# FAT_main_board.net
KiCad netlist of a schematic drawn in EAGLE
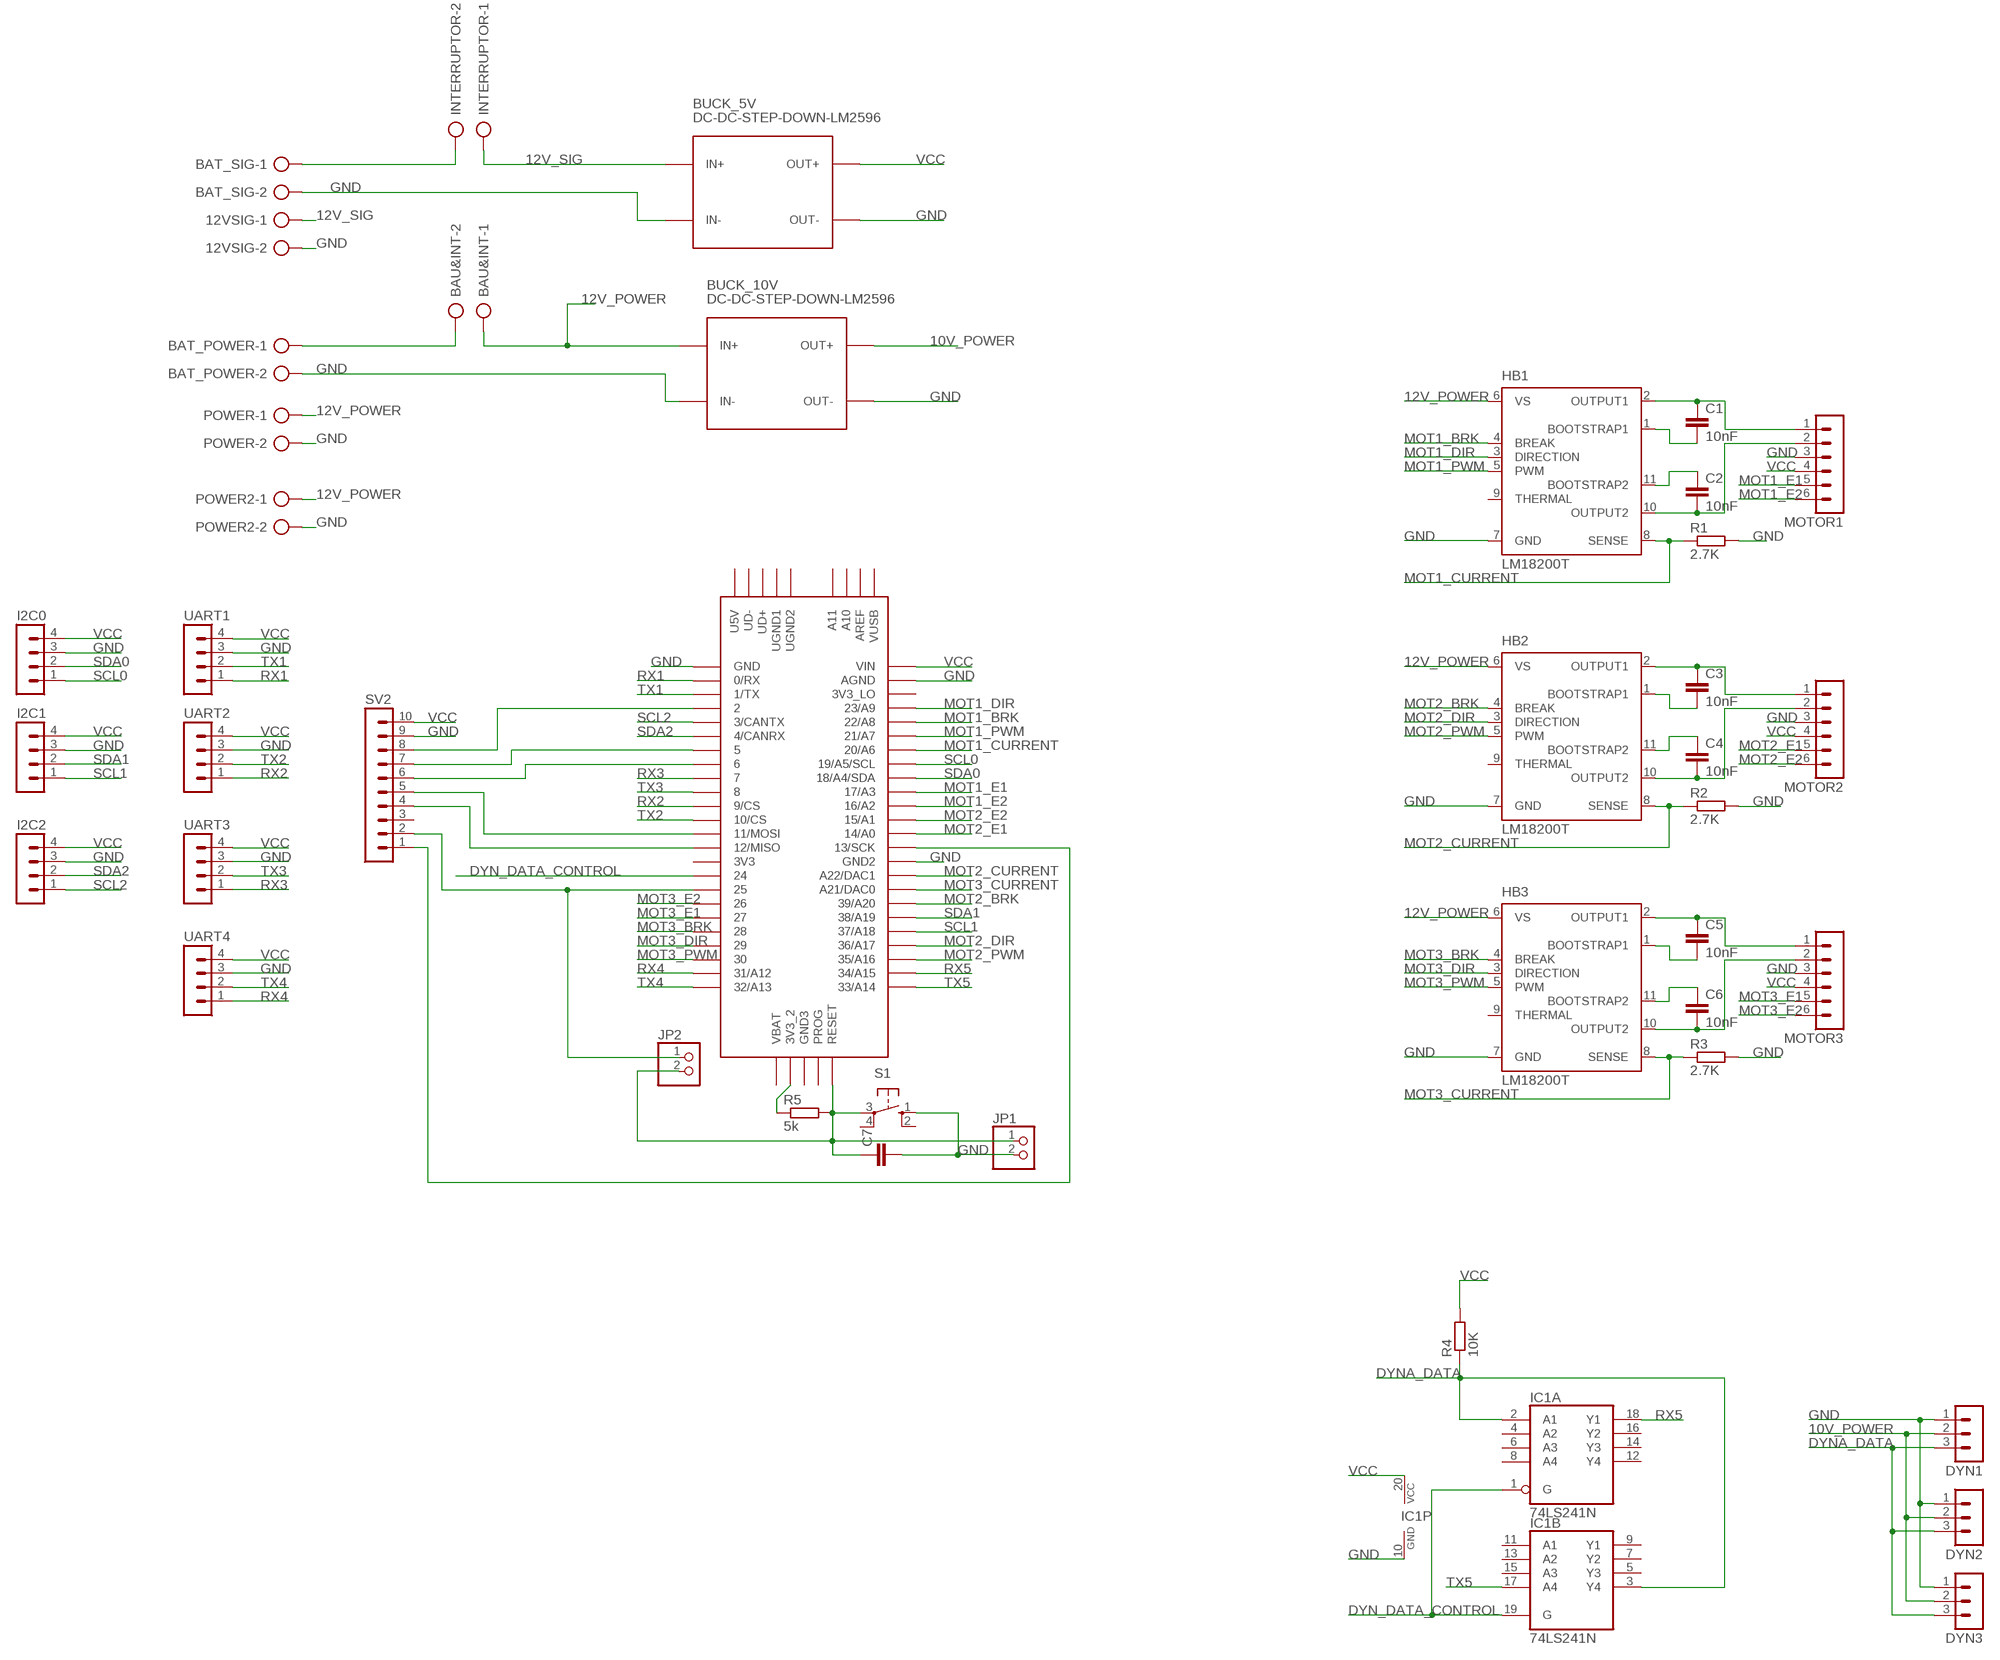
[diagram p0: schematic, sheet 1]

(export (version "E")
  (design (tool "Eeschema 10.0.6"))
  (components
    (comp (ref "12VSIG")
      (value "AK300/2")
      (footprint "eagle-import:AK300_2")
      (libsource (lib "eagle-import") (part "AK300/2"))
    )
    (comp (ref "BAT_POWER")
      (value "AK300/2")
      (footprint "eagle-import:AK300_2")
      (libsource (lib "eagle-import") (part "AK300/2"))
    )
    (comp (ref "BAT_SIG")
      (value "AK300/2")
      (footprint "eagle-import:AK300_2")
      (libsource (lib "eagle-import") (part "AK300/2"))
    )
    (comp (ref "BAU&INT")
      (value "AK300/2")
      (footprint "eagle-import:AK300_2")
      (libsource (lib "eagle-import") (part "AK300/2"))
    )
    (comp (ref "BUCK_5V")
      (value "DC-DC-STEP-DOWN-LM2596")
      (footprint "eagle-import:DC-DC-STEP-DOWN-LM2596")
      (libsource (lib "eagle-import") (part "DC-DC-STEP-DOWN-LM2596"))
    )
    (comp (ref "BUCK_10V")
      (value "DC-DC-STEP-DOWN-LM2596")
      (footprint "eagle-import:DC-DC-STEP-DOWN-LM2596")
      (libsource (lib "eagle-import") (part "DC-DC-STEP-DOWN-LM2596"))
    )
    (comp (ref "C1")
      (value "10nF")
      (footprint "eagle-import:C050-035X075")
      (libsource (lib "eagle-import") (part "resistor_C-EU050-035X075"))
    )
    (comp (ref "C2")
      (value "10nF")
      (footprint "eagle-import:C050-035X075")
      (libsource (lib "eagle-import") (part "resistor_C-EU050-035X075"))
    )
    (comp (ref "C3")
      (value "10nF")
      (footprint "eagle-import:C050-035X075")
      (libsource (lib "eagle-import") (part "resistor_C-EU050-035X075"))
    )
    (comp (ref "C4")
      (value "10nF")
      (footprint "eagle-import:C050-035X075")
      (libsource (lib "eagle-import") (part "resistor_C-EU050-035X075"))
    )
    (comp (ref "C5")
      (value "10nF")
      (footprint "eagle-import:C050-035X075")
      (libsource (lib "eagle-import") (part "resistor_C-EU050-035X075"))
    )
    (comp (ref "C6")
      (value "10nF")
      (footprint "eagle-import:C050-035X075")
      (libsource (lib "eagle-import") (part "resistor_C-EU050-035X075"))
    )
    (comp (ref "C7")
      (value "C-EU025-025X050")
      (footprint "eagle-import:C025-025X050")
      (libsource (lib "eagle-import") (part "C-EU025-025X050"))
    )
    (comp (ref "DYN1")
      (value "MA03-1")
      (footprint "eagle-import:MA03-1")
      (libsource (lib "eagle-import") (part "MA03-1"))
    )
    (comp (ref "DYN2")
      (value "MA03-1")
      (footprint "eagle-import:MA03-1")
      (libsource (lib "eagle-import") (part "MA03-1"))
    )
    (comp (ref "DYN3")
      (value "MA03-1")
      (footprint "eagle-import:MA03-1")
      (libsource (lib "eagle-import") (part "MA03-1"))
    )
    (comp (ref "HB1")
      (value "LM18200T")
      (footprint "eagle-import:TO-220-11")
      (libsource (lib "eagle-import") (part "LM18200T"))
    )
    (comp (ref "HB2")
      (value "LM18200T")
      (footprint "eagle-import:TO-220-11")
      (libsource (lib "eagle-import") (part "LM18200T"))
    )
    (comp (ref "HB3")
      (value "LM18200T")
      (footprint "eagle-import:TO-220-11")
      (libsource (lib "eagle-import") (part "LM18200T"))
    )
    (comp (ref "I2C0")
      (value "MA04-1")
      (footprint "eagle-import:MA04-1")
      (libsource (lib "eagle-import") (part "MA04-1"))
    )
    (comp (ref "I2C1")
      (value "MA04-1")
      (footprint "eagle-import:MA04-1")
      (libsource (lib "eagle-import") (part "MA04-1"))
    )
    (comp (ref "I2C2")
      (value "MA04-1")
      (footprint "eagle-import:MA04-1")
      (libsource (lib "eagle-import") (part "MA04-1"))
    )
    (comp (ref "IC1")
      (value "74LS241N")
      (footprint "eagle-import:DIL20")
      (libsource (lib "eagle-import") (part "74241NLS"))
    )
    (comp (ref "INTERRUPTOR")
      (value "AK300/2")
      (footprint "eagle-import:AK300_2")
      (libsource (lib "eagle-import") (part "AK300/2"))
    )
    (comp (ref "JP1")
      (value "PINHD-1X2")
      (footprint "eagle-import:1X02")
      (libsource (lib "eagle-import") (part "PINHD-1X2"))
    )
    (comp (ref "JP2")
      (value "PINHD-1X2")
      (footprint "eagle-import:1X02")
      (libsource (lib "eagle-import") (part "PINHD-1X2"))
    )
    (comp (ref "MOTOR1")
      (value "MA06-1")
      (footprint "eagle-import:MA06-1")
      (libsource (lib "eagle-import") (part "MA06-1"))
    )
    (comp (ref "MOTOR2")
      (value "MA06-1")
      (footprint "eagle-import:MA06-1")
      (libsource (lib "eagle-import") (part "MA06-1"))
    )
    (comp (ref "MOTOR3")
      (value "MA06-1")
      (footprint "eagle-import:MA06-1")
      (libsource (lib "eagle-import") (part "MA06-1"))
    )
    (comp (ref "POWER")
      (value "AK300/2")
      (footprint "eagle-import:AK300_2")
      (libsource (lib "eagle-import") (part "AK300/2"))
    )
    (comp (ref "POWER2")
      (value "AK300/2")
      (footprint "eagle-import:AK300_2")
      (libsource (lib "eagle-import") (part "AK300/2"))
    )
    (comp (ref "R1")
      (value "2.7K")
      (footprint "eagle-import:0204_7")
      (libsource (lib "eagle-import") (part "resistor_R-EU_0204/7"))
    )
    (comp (ref "R2")
      (value "2.7K")
      (footprint "eagle-import:0204_7")
      (libsource (lib "eagle-import") (part "resistor_R-EU_0204/7"))
    )
    (comp (ref "R3")
      (value "2.7K")
      (footprint "eagle-import:0204_7")
      (libsource (lib "eagle-import") (part "resistor_R-EU_0204/7"))
    )
    (comp (ref "R4")
      (value "10K")
      (footprint "eagle-import:0204_7")
      (libsource (lib "eagle-import") (part "resistor_R-EU_0204/7"))
    )
    (comp (ref "R5")
      (value "5k")
      (footprint "eagle-import:0204_7")
      (libsource (lib "eagle-import") (part "R-EU_0204/7"))
    )
    (comp (ref "S1")
      (value "10-XX")
      (footprint "eagle-import:B3F-10XX")
      (fields (field (name "MPN") "B3F-1000"))
      (libsource (lib "eagle-import") (part "10-XX"))
    )
    (comp (ref "SV2")
      (value "MA10-1")
      (footprint "eagle-import:MA10-1")
      (libsource (lib "eagle-import") (part "MA10-1"))
    )
    (comp (ref "U$1")
      (value "TEENSY_3.5/3.6")
      (footprint "eagle-import:TEENSY_3.5_3.6")
      (libsource (lib "eagle-import") (part "TEENSY_3.5/3.6"))
    )
    (comp (ref "UART1")
      (value "MA04-1")
      (footprint "eagle-import:MA04-1")
      (libsource (lib "eagle-import") (part "MA04-1"))
    )
    (comp (ref "UART2")
      (value "MA04-1")
      (footprint "eagle-import:MA04-1")
      (libsource (lib "eagle-import") (part "MA04-1"))
    )
    (comp (ref "UART3")
      (value "MA04-1")
      (footprint "eagle-import:MA04-1")
      (libsource (lib "eagle-import") (part "MA04-1"))
    )
    (comp (ref "UART4")
      (value "MA04-1")
      (footprint "eagle-import:MA04-1")
      (libsource (lib "eagle-import") (part "MA04-1"))
    )
  )
  (nets
    (net (code "1") (name "/10V_POWER") (class "Default")
      (node (ref "BUCK_10V") (pin "OUT+") (pinfunction "OUT+_OUT+") (pintype "bidirectional"))
      (node (ref "DYN1") (pin "2") (pinfunction "2_2") (pintype "passive"))
      (node (ref "DYN2") (pin "2") (pinfunction "2_2") (pintype "passive"))
      (node (ref "DYN3") (pin "2") (pinfunction "2_2") (pintype "passive"))
    )
    (net (code "2") (name "/12V_POWER") (class "Default")
      (node (ref "BAU&INT") (pin "1") (pinfunction "KL_1") (pintype "passive"))
      (node (ref "BUCK_10V") (pin "IN+") (pinfunction "IN+_IN+") (pintype "bidirectional"))
      (node (ref "HB1") (pin "6") (pinfunction "VS_6") (pintype "power_in"))
      (node (ref "HB2") (pin "6") (pinfunction "VS_6") (pintype "power_in"))
      (node (ref "HB3") (pin "6") (pinfunction "VS_6") (pintype "power_in"))
      (node (ref "POWER") (pin "1") (pinfunction "KL_1") (pintype "passive"))
      (node (ref "POWER2") (pin "1") (pinfunction "KL_1") (pintype "passive"))
    )
    (net (code "3") (name "/12V_SIG") (class "Default")
      (node (ref "12VSIG") (pin "1") (pinfunction "KL_1") (pintype "passive"))
      (node (ref "BUCK_5V") (pin "IN+") (pinfunction "IN+_IN+") (pintype "bidirectional"))
      (node (ref "INTERRUPTOR") (pin "1") (pinfunction "KL_1") (pintype "passive"))
    )
    (net (code "4") (name "/DYNA_DATA") (class "Default")
      (node (ref "DYN1") (pin "3") (pinfunction "3_3") (pintype "passive"))
      (node (ref "DYN2") (pin "3") (pinfunction "3_3") (pintype "passive"))
      (node (ref "DYN3") (pin "3") (pinfunction "3_3") (pintype "passive"))
      (node (ref "IC1") (pin "2") (pinfunction "A1_2") (pintype "input"))
      (node (ref "IC1") (pin "3") (pinfunction "Y4_3") (pintype "tri_state"))
      (node (ref "R4") (pin "1") (pinfunction "1_1") (pintype "passive"))
    )
    (net (code "5") (name "/DYN_DATA_CONTROL") (class "Default")
      (node (ref "IC1") (pin "1") (pinfunction "G_1") (pintype "input"))
      (node (ref "IC1") (pin "19") (pinfunction "G_19") (pintype "input"))
      (node (ref "U$1") (pin "24") (pinfunction "24_24") (pintype "bidirectional"))
    )
    (net (code "6") (name "/GND") (class "Default")
      (node (ref "12VSIG") (pin "2") (pinfunction "KL_2") (pintype "passive"))
      (node (ref "BAT_POWER") (pin "2") (pinfunction "KL_2") (pintype "passive"))
      (node (ref "BAT_SIG") (pin "2") (pinfunction "KL_2") (pintype "passive"))
      (node (ref "BUCK_10V") (pin "IN-") (pinfunction "IN-_IN-") (pintype "bidirectional"))
      (node (ref "BUCK_10V") (pin "OUT-") (pinfunction "OUT-_OUT-") (pintype "bidirectional"))
      (node (ref "BUCK_5V") (pin "IN-") (pinfunction "IN-_IN-") (pintype "bidirectional"))
      (node (ref "BUCK_5V") (pin "OUT-") (pinfunction "OUT-_OUT-") (pintype "bidirectional"))
      (node (ref "C7") (pin "2") (pinfunction "2_2") (pintype "passive"))
      (node (ref "DYN1") (pin "1") (pinfunction "1_1") (pintype "passive"))
      (node (ref "DYN2") (pin "1") (pinfunction "1_1") (pintype "passive"))
      (node (ref "DYN3") (pin "1") (pinfunction "1_1") (pintype "passive"))
      (node (ref "HB1") (pin "7") (pinfunction "GND_7") (pintype "power_in"))
      (node (ref "HB2") (pin "7") (pinfunction "GND_7") (pintype "power_in"))
      (node (ref "HB3") (pin "7") (pinfunction "GND_7") (pintype "power_in"))
      (node (ref "I2C0") (pin "3") (pinfunction "3_3") (pintype "passive"))
      (node (ref "I2C1") (pin "3") (pinfunction "3_3") (pintype "passive"))
      (node (ref "I2C2") (pin "3") (pinfunction "3_3") (pintype "passive"))
      (node (ref "IC1") (pin "10") (pinfunction "GND_10") (pintype "power_in"))
      (node (ref "JP1") (pin "2") (pinfunction "2_2") (pintype "passive"))
      (node (ref "MOTOR1") (pin "3") (pinfunction "3_3") (pintype "passive"))
      (node (ref "MOTOR2") (pin "3") (pinfunction "3_3") (pintype "passive"))
      (node (ref "MOTOR3") (pin "3") (pinfunction "3_3") (pintype "passive"))
      (node (ref "POWER") (pin "2") (pinfunction "KL_2") (pintype "passive"))
      (node (ref "POWER2") (pin "2") (pinfunction "KL_2") (pintype "passive"))
      (node (ref "R1") (pin "2") (pinfunction "2_2") (pintype "passive"))
      (node (ref "R2") (pin "2") (pinfunction "2_2") (pintype "passive"))
      (node (ref "R3") (pin "2") (pinfunction "2_2") (pintype "passive"))
      (node (ref "S1") (pin "1") (pinfunction "S_1") (pintype "passive"))
      (node (ref "SV2") (pin "9") (pinfunction "9_9") (pintype "passive"))
      (node (ref "U$1") (pin "AGND") (pinfunction "AGND_AGND") (pintype "bidirectional"))
      (node (ref "U$1") (pin "GND") (pinfunction "GND_GND") (pintype "bidirectional"))
      (node (ref "U$1") (pin "GND2") (pinfunction "GND2_GND2") (pintype "bidirectional"))
      (node (ref "UART1") (pin "3") (pinfunction "3_3") (pintype "passive"))
      (node (ref "UART2") (pin "3") (pinfunction "3_3") (pintype "passive"))
      (node (ref "UART3") (pin "3") (pinfunction "3_3") (pintype "passive"))
      (node (ref "UART4") (pin "3") (pinfunction "3_3") (pintype "passive"))
    )
    (net (code "7") (name "/MOT1_BRK") (class "Default")
      (node (ref "HB1") (pin "4") (pinfunction "BREAK_4") (pintype "input"))
      (node (ref "U$1") (pin "22/A8") (pinfunction "22/A8_22/A8") (pintype "bidirectional"))
    )
    (net (code "8") (name "/MOT1_CURRENT") (class "Default")
      (node (ref "HB1") (pin "8") (pinfunction "SENSE_8") (pintype "output"))
      (node (ref "R1") (pin "1") (pinfunction "1_1") (pintype "passive"))
      (node (ref "U$1") (pin "20/A6") (pinfunction "20/A6_20/A6") (pintype "bidirectional"))
    )
    (net (code "9") (name "/MOT1_DIR") (class "Default")
      (node (ref "HB1") (pin "3") (pinfunction "DIRECTION_3") (pintype "input"))
      (node (ref "U$1") (pin "23/A9") (pinfunction "23/A9_23/A9") (pintype "bidirectional"))
    )
    (net (code "10") (name "/MOT1_E1") (class "Default")
      (node (ref "MOTOR1") (pin "5") (pinfunction "5_5") (pintype "passive"))
      (node (ref "U$1") (pin "17/A3") (pinfunction "17/A3_17/A3") (pintype "bidirectional"))
    )
    (net (code "11") (name "/MOT1_E2") (class "Default")
      (node (ref "MOTOR1") (pin "6") (pinfunction "6_6") (pintype "passive"))
      (node (ref "U$1") (pin "16/A2") (pinfunction "16/A2_16/A2") (pintype "bidirectional"))
    )
    (net (code "12") (name "/MOT1_PWM") (class "Default")
      (node (ref "HB1") (pin "5") (pinfunction "PWM_5") (pintype "input"))
      (node (ref "U$1") (pin "21/A7") (pinfunction "21/A7_21/A7") (pintype "bidirectional"))
    )
    (net (code "13") (name "/MOT2_BRK") (class "Default")
      (node (ref "HB2") (pin "4") (pinfunction "BREAK_4") (pintype "input"))
      (node (ref "U$1") (pin "39/A20") (pinfunction "39/A20_39/A20") (pintype "bidirectional"))
    )
    (net (code "14") (name "/MOT2_CURRENT") (class "Default")
      (node (ref "HB2") (pin "8") (pinfunction "SENSE_8") (pintype "output"))
      (node (ref "R2") (pin "1") (pinfunction "1_1") (pintype "passive"))
      (node (ref "U$1") (pin "A22/DAC1") (pinfunction "A22/DAC1_A22/DAC1") (pintype "bidirectional"))
    )
    (net (code "15") (name "/MOT2_DIR") (class "Default")
      (node (ref "HB2") (pin "3") (pinfunction "DIRECTION_3") (pintype "input"))
      (node (ref "U$1") (pin "36/A17") (pinfunction "36/A17_36/A17") (pintype "bidirectional"))
    )
    (net (code "16") (name "/MOT2_E1") (class "Default")
      (node (ref "MOTOR2") (pin "5") (pinfunction "5_5") (pintype "passive"))
      (node (ref "U$1") (pin "14/A0") (pinfunction "14/A0_14/A0") (pintype "bidirectional"))
    )
    (net (code "17") (name "/MOT2_E2") (class "Default")
      (node (ref "MOTOR2") (pin "6") (pinfunction "6_6") (pintype "passive"))
      (node (ref "U$1") (pin "15/A1") (pinfunction "15/A1_15/A1") (pintype "bidirectional"))
    )
    (net (code "18") (name "/MOT2_PWM") (class "Default")
      (node (ref "HB2") (pin "5") (pinfunction "PWM_5") (pintype "input"))
      (node (ref "U$1") (pin "35/A16") (pinfunction "35/A16_35/A16") (pintype "bidirectional"))
    )
    (net (code "19") (name "/MOT3_BRK") (class "Default")
      (node (ref "HB3") (pin "4") (pinfunction "BREAK_4") (pintype "input"))
      (node (ref "U$1") (pin "28") (pinfunction "28_28") (pintype "bidirectional"))
    )
    (net (code "20") (name "/MOT3_CURRENT") (class "Default")
      (node (ref "HB3") (pin "8") (pinfunction "SENSE_8") (pintype "output"))
      (node (ref "R3") (pin "1") (pinfunction "1_1") (pintype "passive"))
      (node (ref "U$1") (pin "21/DAC0") (pinfunction "A21/DAC0_21/DAC0") (pintype "bidirectional"))
    )
    (net (code "21") (name "/MOT3_DIR") (class "Default")
      (node (ref "HB3") (pin "3") (pinfunction "DIRECTION_3") (pintype "input"))
      (node (ref "U$1") (pin "29") (pinfunction "29_29") (pintype "bidirectional"))
    )
    (net (code "22") (name "/MOT3_E1") (class "Default")
      (node (ref "MOTOR3") (pin "5") (pinfunction "5_5") (pintype "passive"))
      (node (ref "U$1") (pin "27") (pinfunction "27_27") (pintype "bidirectional"))
    )
    (net (code "23") (name "/MOT3_E2") (class "Default")
      (node (ref "MOTOR3") (pin "6") (pinfunction "6_6") (pintype "passive"))
      (node (ref "U$1") (pin "26") (pinfunction "26_26") (pintype "bidirectional"))
    )
    (net (code "24") (name "/MOT3_PWM") (class "Default")
      (node (ref "HB3") (pin "5") (pinfunction "PWM_5") (pintype "input"))
      (node (ref "U$1") (pin "30") (pinfunction "30_30") (pintype "bidirectional"))
    )
    (net (code "25") (name "/RX1") (class "Default")
      (node (ref "U$1") (pin "0/RX") (pinfunction "0/RX_0/RX") (pintype "bidirectional"))
      (node (ref "UART1") (pin "1") (pinfunction "1_1") (pintype "passive"))
    )
    (net (code "26") (name "/RX2") (class "Default")
      (node (ref "U$1") (pin "9/CS") (pinfunction "9/CS_9/CS") (pintype "bidirectional"))
      (node (ref "UART2") (pin "1") (pinfunction "1_1") (pintype "passive"))
    )
    (net (code "27") (name "/RX3") (class "Default")
      (node (ref "U$1") (pin "7") (pinfunction "7_7") (pintype "bidirectional"))
      (node (ref "UART3") (pin "1") (pinfunction "1_1") (pintype "passive"))
    )
    (net (code "28") (name "/RX4") (class "Default")
      (node (ref "U$1") (pin "31/A12") (pinfunction "31/A12_31/A12") (pintype "bidirectional"))
      (node (ref "UART4") (pin "1") (pinfunction "1_1") (pintype "passive"))
    )
    (net (code "29") (name "/RX5") (class "Default")
      (node (ref "IC1") (pin "18") (pinfunction "Y1_18") (pintype "tri_state"))
      (node (ref "U$1") (pin "34/A15") (pinfunction "34/A15_34/A15") (pintype "bidirectional"))
    )
    (net (code "30") (name "/SCL0") (class "Default")
      (node (ref "I2C0") (pin "1") (pinfunction "1_1") (pintype "passive"))
      (node (ref "U$1") (pin "19/A5/SCL") (pinfunction "19/A5/SCL_19/A5/SCL") (pintype "bidirectional"))
    )
    (net (code "31") (name "/SCL1") (class "Default")
      (node (ref "I2C1") (pin "1") (pinfunction "1_1") (pintype "passive"))
      (node (ref "U$1") (pin "37/A18") (pinfunction "37/A18_37/A18") (pintype "bidirectional"))
    )
    (net (code "32") (name "/SCL2") (class "Default")
      (node (ref "I2C2") (pin "1") (pinfunction "1_1") (pintype "passive"))
      (node (ref "U$1") (pin "3/CANTX") (pinfunction "3/CANTX_3/CANTX") (pintype "bidirectional"))
    )
    (net (code "33") (name "/SDA0") (class "Default")
      (node (ref "I2C0") (pin "2") (pinfunction "2_2") (pintype "passive"))
      (node (ref "U$1") (pin "18/A4/SDA") (pinfunction "18/A4/SDA_18/A4/SDA") (pintype "bidirectional"))
    )
    (net (code "34") (name "/SDA1") (class "Default")
      (node (ref "I2C1") (pin "2") (pinfunction "2_2") (pintype "passive"))
      (node (ref "U$1") (pin "38/A19") (pinfunction "38/A19_38/A19") (pintype "bidirectional"))
    )
    (net (code "35") (name "/SDA2") (class "Default")
      (node (ref "I2C2") (pin "2") (pinfunction "2_2") (pintype "passive"))
      (node (ref "U$1") (pin "4/CANRX") (pinfunction "4/CANRX_4/CANRX") (pintype "bidirectional"))
    )
    (net (code "36") (name "/TX1") (class "Default")
      (node (ref "U$1") (pin "1/TX") (pinfunction "1/TX_1/TX") (pintype "bidirectional"))
      (node (ref "UART1") (pin "2") (pinfunction "2_2") (pintype "passive"))
    )
    (net (code "37") (name "/TX2") (class "Default")
      (node (ref "U$1") (pin "10/CS") (pinfunction "10/CS_10/CS") (pintype "bidirectional"))
      (node (ref "UART2") (pin "2") (pinfunction "2_2") (pintype "passive"))
    )
    (net (code "38") (name "/TX3") (class "Default")
      (node (ref "U$1") (pin "8") (pinfunction "8_8") (pintype "bidirectional"))
      (node (ref "UART3") (pin "2") (pinfunction "2_2") (pintype "passive"))
    )
    (net (code "39") (name "/TX4") (class "Default")
      (node (ref "U$1") (pin "32/A13") (pinfunction "32/A13_32/A13") (pintype "bidirectional"))
      (node (ref "UART4") (pin "2") (pinfunction "2_2") (pintype "passive"))
    )
    (net (code "40") (name "/TX5") (class "Default")
      (node (ref "IC1") (pin "17") (pinfunction "A4_17") (pintype "input"))
      (node (ref "U$1") (pin "33/A14") (pinfunction "33/A14_33/A14") (pintype "bidirectional"))
    )
    (net (code "41") (name "/VCC") (class "Default")
      (node (ref "BUCK_5V") (pin "OUT+") (pinfunction "OUT+_OUT+") (pintype "bidirectional"))
      (node (ref "I2C0") (pin "4") (pinfunction "4_4") (pintype "passive"))
      (node (ref "I2C1") (pin "4") (pinfunction "4_4") (pintype "passive"))
      (node (ref "I2C2") (pin "4") (pinfunction "4_4") (pintype "passive"))
      (node (ref "IC1") (pin "20") (pinfunction "VCC_20") (pintype "power_in"))
      (node (ref "MOTOR1") (pin "4") (pinfunction "4_4") (pintype "passive"))
      (node (ref "MOTOR2") (pin "4") (pinfunction "4_4") (pintype "passive"))
      (node (ref "MOTOR3") (pin "4") (pinfunction "4_4") (pintype "passive"))
      (node (ref "R4") (pin "2") (pinfunction "2_2") (pintype "passive"))
      (node (ref "SV2") (pin "10") (pinfunction "10_10") (pintype "passive"))
      (node (ref "U$1") (pin "VIN") (pinfunction "VIN_VIN") (pintype "bidirectional"))
      (node (ref "UART1") (pin "4") (pinfunction "4_4") (pintype "passive"))
      (node (ref "UART2") (pin "4") (pinfunction "4_4") (pintype "passive"))
      (node (ref "UART3") (pin "4") (pinfunction "4_4") (pintype "passive"))
      (node (ref "UART4") (pin "4") (pinfunction "4_4") (pintype "passive"))
    )
    (net (code "42") (name "Net-(BAT_POWERA-KL)") (class "Default")
      (node (ref "BAT_POWER") (pin "1") (pinfunction "KL_1") (pintype "passive"))
      (node (ref "BAU&INT") (pin "2") (pinfunction "KL_2") (pintype "passive"))
    )
    (net (code "43") (name "Net-(BAT_SIGA-KL)") (class "Default")
      (node (ref "BAT_SIG") (pin "1") (pinfunction "KL_1") (pintype "passive"))
      (node (ref "INTERRUPTOR") (pin "2") (pinfunction "KL_2") (pintype "passive"))
    )
    (net (code "44") (name "Net-(HB1-BOOTSTRAP1)") (class "Default")
      (node (ref "C1") (pin "2") (pinfunction "2_2") (pintype "passive"))
      (node (ref "HB1") (pin "1") (pinfunction "BOOTSTRAP1_1") (pintype "input"))
    )
    (net (code "45") (name "Net-(HB1-BOOTSTRAP2)") (class "Default")
      (node (ref "C2") (pin "1") (pinfunction "1_1") (pintype "passive"))
      (node (ref "HB1") (pin "11") (pinfunction "BOOTSTRAP2_11") (pintype "input"))
    )
    (net (code "46") (name "Net-(HB1-OUTPUT1)") (class "Default")
      (node (ref "C1") (pin "1") (pinfunction "1_1") (pintype "passive"))
      (node (ref "HB1") (pin "2") (pinfunction "OUTPUT1_2") (pintype "output"))
      (node (ref "MOTOR1") (pin "1") (pinfunction "1_1") (pintype "passive"))
    )
    (net (code "47") (name "Net-(HB1-OUTPUT2)") (class "Default")
      (node (ref "C2") (pin "2") (pinfunction "2_2") (pintype "passive"))
      (node (ref "HB1") (pin "10") (pinfunction "OUTPUT2_10") (pintype "output"))
      (node (ref "MOTOR1") (pin "2") (pinfunction "2_2") (pintype "passive"))
    )
    (net (code "48") (name "Net-(HB2-BOOTSTRAP1)") (class "Default")
      (node (ref "C3") (pin "2") (pinfunction "2_2") (pintype "passive"))
      (node (ref "HB2") (pin "1") (pinfunction "BOOTSTRAP1_1") (pintype "input"))
    )
    (net (code "49") (name "Net-(HB2-BOOTSTRAP2)") (class "Default")
      (node (ref "C4") (pin "1") (pinfunction "1_1") (pintype "passive"))
      (node (ref "HB2") (pin "11") (pinfunction "BOOTSTRAP2_11") (pintype "input"))
    )
    (net (code "50") (name "Net-(HB2-OUTPUT1)") (class "Default")
      (node (ref "C3") (pin "1") (pinfunction "1_1") (pintype "passive"))
      (node (ref "HB2") (pin "2") (pinfunction "OUTPUT1_2") (pintype "output"))
      (node (ref "MOTOR2") (pin "1") (pinfunction "1_1") (pintype "passive"))
    )
    (net (code "51") (name "Net-(HB2-OUTPUT2)") (class "Default")
      (node (ref "C4") (pin "2") (pinfunction "2_2") (pintype "passive"))
      (node (ref "HB2") (pin "10") (pinfunction "OUTPUT2_10") (pintype "output"))
      (node (ref "MOTOR2") (pin "2") (pinfunction "2_2") (pintype "passive"))
    )
    (net (code "52") (name "Net-(HB3-BOOTSTRAP1)") (class "Default")
      (node (ref "C5") (pin "2") (pinfunction "2_2") (pintype "passive"))
      (node (ref "HB3") (pin "1") (pinfunction "BOOTSTRAP1_1") (pintype "input"))
    )
    (net (code "53") (name "Net-(HB3-BOOTSTRAP2)") (class "Default")
      (node (ref "C6") (pin "1") (pinfunction "1_1") (pintype "passive"))
      (node (ref "HB3") (pin "11") (pinfunction "BOOTSTRAP2_11") (pintype "input"))
    )
    (net (code "54") (name "Net-(HB3-OUTPUT1)") (class "Default")
      (node (ref "C5") (pin "1") (pinfunction "1_1") (pintype "passive"))
      (node (ref "HB3") (pin "2") (pinfunction "OUTPUT1_2") (pintype "output"))
      (node (ref "MOTOR3") (pin "1") (pinfunction "1_1") (pintype "passive"))
    )
    (net (code "55") (name "Net-(HB3-OUTPUT2)") (class "Default")
      (node (ref "C6") (pin "2") (pinfunction "2_2") (pintype "passive"))
      (node (ref "HB3") (pin "10") (pinfunction "OUTPUT2_10") (pintype "output"))
      (node (ref "MOTOR3") (pin "2") (pinfunction "2_2") (pintype "passive"))
    )
    (net (code "56") (name "Net-(JP2-Pad1)") (class "Default")
      (node (ref "JP2") (pin "1") (pinfunction "1_1") (pintype "passive"))
      (node (ref "SV2") (pin "2") (pinfunction "2_2") (pintype "passive"))
      (node (ref "U$1") (pin "25") (pinfunction "25_25") (pintype "bidirectional"))
    )
    (net (code "57") (name "Net-(R5-Pad1)") (class "Default")
      (node (ref "R5") (pin "1") (pinfunction "1_1") (pintype "passive"))
      (node (ref "U$1") (pin "3V3_2") (pinfunction "3V3_2_3V3_2") (pintype "bidirectional"))
    )
    (net (code "58") (name "Net-(S1-P)") (class "Default")
      (node (ref "C7") (pin "1") (pinfunction "1_1") (pintype "passive"))
      (node (ref "JP1") (pin "1") (pinfunction "1_1") (pintype "passive"))
      (node (ref "JP2") (pin "2") (pinfunction "2_2") (pintype "passive"))
      (node (ref "R5") (pin "2") (pinfunction "2_2") (pintype "passive"))
      (node (ref "S1") (pin "3") (pinfunction "P_3") (pintype "passive"))
      (node (ref "U$1") (pin "RESET") (pinfunction "RESET_RESET") (pintype "bidirectional"))
    )
    (net (code "59") (name "Net-(SV2-Pad1)") (class "Default")
      (node (ref "SV2") (pin "1") (pinfunction "1_1") (pintype "passive"))
      (node (ref "U$1") (pin "13/SCK") (pinfunction "13/SCK_13/SCK") (pintype "bidirectional"))
    )
    (net (code "60") (name "Net-(SV2-Pad4)") (class "Default")
      (node (ref "SV2") (pin "4") (pinfunction "4_4") (pintype "passive"))
      (node (ref "U$1") (pin "12/MISO") (pinfunction "12/MISO_12/MISO") (pintype "bidirectional"))
    )
    (net (code "61") (name "Net-(SV2-Pad5)") (class "Default")
      (node (ref "SV2") (pin "5") (pinfunction "5_5") (pintype "passive"))
      (node (ref "U$1") (pin "11/MOSI") (pinfunction "11/MOSI_11/MOSI") (pintype "bidirectional"))
    )
    (net (code "62") (name "Net-(SV2-Pad6)") (class "Default")
      (node (ref "SV2") (pin "6") (pinfunction "6_6") (pintype "passive"))
      (node (ref "U$1") (pin "6") (pinfunction "6_6") (pintype "bidirectional"))
    )
    (net (code "63") (name "Net-(SV2-Pad7)") (class "Default")
      (node (ref "SV2") (pin "7") (pinfunction "7_7") (pintype "passive"))
      (node (ref "U$1") (pin "5") (pinfunction "5_5") (pintype "bidirectional"))
    )
    (net (code "64") (name "Net-(SV2-Pad8)") (class "Default")
      (node (ref "SV2") (pin "8") (pinfunction "8_8") (pintype "passive"))
      (node (ref "U$1") (pin "2") (pinfunction "2_2") (pintype "bidirectional"))
    )
    (net (code "65") (name "unconnected-(HB1-THERMAL-Pad9)") (class "Default")
      (node (ref "HB1") (pin "9") (pinfunction "THERMAL_9") (pintype "output"))
    )
    (net (code "66") (name "unconnected-(HB2-THERMAL-Pad9)") (class "Default")
      (node (ref "HB2") (pin "9") (pinfunction "THERMAL_9") (pintype "output"))
    )
    (net (code "67") (name "unconnected-(HB3-THERMAL-Pad9)") (class "Default")
      (node (ref "HB3") (pin "9") (pinfunction "THERMAL_9") (pintype "output"))
    )
    (net (code "68") (name "unconnected-(IC1A-A2-Pad4)") (class "Default")
      (node (ref "IC1") (pin "4") (pinfunction "A2_4") (pintype "input"))
    )
    (net (code "69") (name "unconnected-(IC1A-A3-Pad6)") (class "Default")
      (node (ref "IC1") (pin "6") (pinfunction "A3_6") (pintype "input"))
    )
    (net (code "70") (name "unconnected-(IC1A-A4-Pad8)") (class "Default")
      (node (ref "IC1") (pin "8") (pinfunction "A4_8") (pintype "input"))
    )
    (net (code "71") (name "unconnected-(IC1A-Y2-Pad16)") (class "Default")
      (node (ref "IC1") (pin "16") (pinfunction "Y2_16") (pintype "tri_state"))
    )
    (net (code "72") (name "unconnected-(IC1A-Y3-Pad14)") (class "Default")
      (node (ref "IC1") (pin "14") (pinfunction "Y3_14") (pintype "tri_state"))
    )
    (net (code "73") (name "unconnected-(IC1A-Y4-Pad12)") (class "Default")
      (node (ref "IC1") (pin "12") (pinfunction "Y4_12") (pintype "tri_state"))
    )
    (net (code "74") (name "unconnected-(IC1B-A1-Pad11)") (class "Default")
      (node (ref "IC1") (pin "11") (pinfunction "A1_11") (pintype "input"))
    )
    (net (code "75") (name "unconnected-(IC1B-A2-Pad13)") (class "Default")
      (node (ref "IC1") (pin "13") (pinfunction "A2_13") (pintype "input"))
    )
    (net (code "76") (name "unconnected-(IC1B-A3-Pad15)") (class "Default")
      (node (ref "IC1") (pin "15") (pinfunction "A3_15") (pintype "input"))
    )
    (net (code "77") (name "unconnected-(IC1B-Y1-Pad9)") (class "Default")
      (node (ref "IC1") (pin "9") (pinfunction "Y1_9") (pintype "tri_state"))
    )
    (net (code "78") (name "unconnected-(IC1B-Y2-Pad7)") (class "Default")
      (node (ref "IC1") (pin "7") (pinfunction "Y2_7") (pintype "tri_state"))
    )
    (net (code "79") (name "unconnected-(IC1B-Y3-Pad5)") (class "Default")
      (node (ref "IC1") (pin "5") (pinfunction "Y3_5") (pintype "tri_state"))
    )
    (net (code "80") (name "unconnected-(S1-P1-Pad4)") (class "Default")
      (node (ref "S1") (pin "4") (pinfunction "P1_4") (pintype "passive"))
    )
    (net (code "81") (name "unconnected-(S1-S1-Pad2)") (class "Default")
      (node (ref "S1") (pin "2") (pinfunction "S1_2") (pintype "passive"))
    )
    (net (code "82") (name "unconnected-(SV2-Pad3)") (class "Default")
      (node (ref "SV2") (pin "3") (pinfunction "3_3") (pintype "passive"))
    )
    (net (code "83") (name "unconnected-(U$1-Pad3V3)") (class "Default")
      (node (ref "U$1") (pin "3V3") (pinfunction "3V3_3V3") (pintype "bidirectional"))
    )
    (net (code "84") (name "unconnected-(U$1-Pad3V3_LO)") (class "Default")
      (node (ref "U$1") (pin "3V3_LO") (pinfunction "3V3_LO_3V3_LO") (pintype "bidirectional"))
    )
    (net (code "85") (name "unconnected-(U$1-PadA10)") (class "Default")
      (node (ref "U$1") (pin "A10") (pinfunction "A10_A10") (pintype "bidirectional"))
    )
    (net (code "86") (name "unconnected-(U$1-PadA11)") (class "Default")
      (node (ref "U$1") (pin "A11") (pinfunction "A11_A11") (pintype "bidirectional"))
    )
    (net (code "87") (name "unconnected-(U$1-PadAREF)") (class "Default")
      (node (ref "U$1") (pin "AREF") (pinfunction "AREF_AREF") (pintype "bidirectional"))
    )
    (net (code "88") (name "unconnected-(U$1-PadGND3)") (class "Default")
      (node (ref "U$1") (pin "GND3") (pinfunction "GND3_GND3") (pintype "bidirectional"))
    )
    (net (code "89") (name "unconnected-(U$1-PadPROG)") (class "Default")
      (node (ref "U$1") (pin "PROG") (pinfunction "PROG_PROG") (pintype "bidirectional"))
    )
    (net (code "90") (name "unconnected-(U$1-PadU5V)") (class "Default")
      (node (ref "U$1") (pin "U5V") (pinfunction "U5V_U5V") (pintype "bidirectional"))
    )
    (net (code "91") (name "unconnected-(U$1-PadUD+)") (class "Default")
      (node (ref "U$1") (pin "UD+") (pinfunction "UD+_UD+") (pintype "bidirectional"))
    )
    (net (code "92") (name "unconnected-(U$1-PadUD-)") (class "Default")
      (node (ref "U$1") (pin "UD-") (pinfunction "UD-_UD-") (pintype "bidirectional"))
    )
    (net (code "93") (name "unconnected-(U$1-PadUGND1)") (class "Default")
      (node (ref "U$1") (pin "UGND1") (pinfunction "UGND1_UGND1") (pintype "bidirectional"))
    )
    (net (code "94") (name "unconnected-(U$1-PadUGND2)") (class "Default")
      (node (ref "U$1") (pin "UGND2") (pinfunction "UGND2_UGND2") (pintype "bidirectional"))
    )
    (net (code "95") (name "unconnected-(U$1-PadVBAT)") (class "Default")
      (node (ref "U$1") (pin "VBAT") (pinfunction "VBAT_VBAT") (pintype "bidirectional"))
    )
    (net (code "96") (name "unconnected-(U$1-PadVUSB)") (class "Default")
      (node (ref "U$1") (pin "VUSB") (pinfunction "VUSB_VUSB") (pintype "bidirectional"))
    )
  )
)
